# LNA.net
KiCad netlist of a schematic drawn in EAGLE
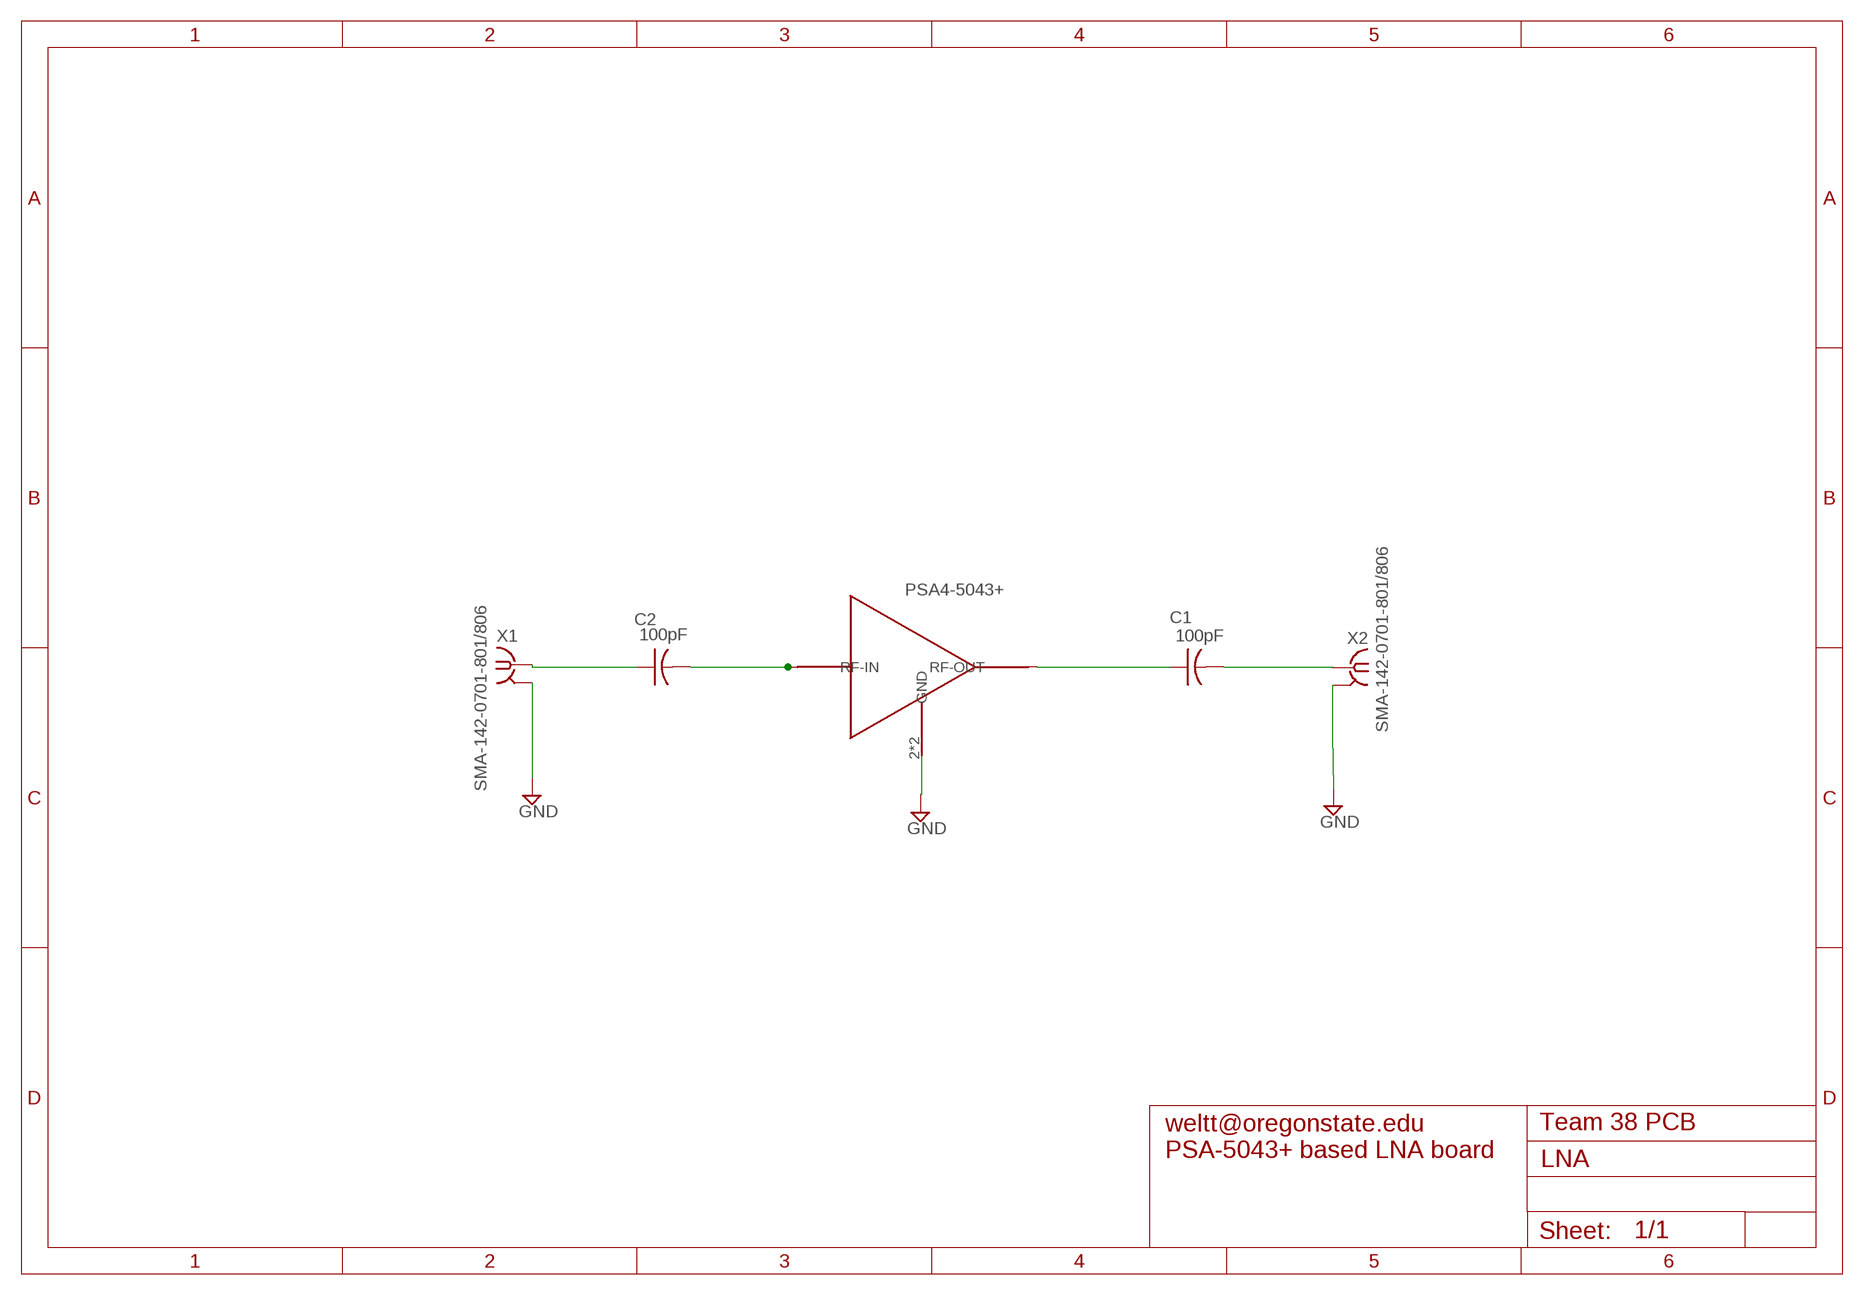
[diagram p0: schematic, sheet 1]

(export (version "E")
  (design (tool "Eeschema 10.0.6"))
  (components
    (comp (ref "C1")
      (value "100pF")
      (footprint "eagle-import:C0402K")
      (libsource (lib "eagle-import") (part "C-USC0402K"))
    )
    (comp (ref "C2")
      (value "100pF")
      (footprint "eagle-import:C0402K")
      (libsource (lib "eagle-import") (part "C-USC0402K"))
    )
    (comp (ref "MMM1362")
      (value "PSA4-5043+")
      (footprint "eagle-import:PSA4-5043+")
      (fields
        (field (name "MF") "Mini-Circuits")
        (field (name "MP") "PSA4-5043+")
        (field (name "PACKAGE") "MMM1362")
        (field (name "PRICE") "2.50")
        (field (name "SPICEPREFIX") "M")
      )
      (libsource (lib "eagle-import") (part "PSA4-5043+"))
    )
    (comp (ref "X1")
      (value "SMA-142-0701-801/806")
      (footprint "eagle-import:J502-ND-142-0701-801_806")
      (fields (field (name "MF") "JOHNSON COMPONENTS") (field (name "MPN") "142-0701-801"))
      (libsource (lib "eagle-import") (part "SMA-142-0701-801/806"))
    )
    (comp (ref "X2")
      (value "SMA-142-0701-801/806")
      (footprint "eagle-import:J502-ND-142-0701-801_806")
      (fields (field (name "MF") "JOHNSON COMPONENTS") (field (name "MPN") "142-0701-801"))
      (libsource (lib "eagle-import") (part "SMA-142-0701-801/806"))
    )
  )
  (nets
    (net (code "1") (name "GND") (class "Default")
      (node (ref "MMM1362") (pin "2") (pinfunction "GND_2") (pintype "bidirectional"))
      (node (ref "MMM1362") (pin "4") (pinfunction "GND_4") (pintype "bidirectional"))
      (node (ref "X1") (pin "G@1") (pinfunction "2_G@1") (pintype "passive"))
      (node (ref "X1") (pin "G@2") (pinfunction "2_G@2") (pintype "passive"))
      (node (ref "X1") (pin "G@3") (pinfunction "2_G@3") (pintype "passive"))
      (node (ref "X1") (pin "G@4") (pinfunction "2_G@4") (pintype "passive"))
      (node (ref "X2") (pin "G@1") (pinfunction "2_G@1") (pintype "passive"))
      (node (ref "X2") (pin "G@2") (pinfunction "2_G@2") (pintype "passive"))
      (node (ref "X2") (pin "G@3") (pinfunction "2_G@3") (pintype "passive"))
      (node (ref "X2") (pin "G@4") (pinfunction "2_G@4") (pintype "passive"))
    )
    (net (code "2") (name "Net-(C1-Pad2)") (class "Default")
      (node (ref "C1") (pin "2") (pinfunction "2_2") (pintype "passive"))
      (node (ref "X2") (pin "1") (pinfunction "1_1") (pintype "passive"))
    )
    (net (code "3") (name "Net-(C2-Pad1)") (class "Default")
      (node (ref "C2") (pin "1") (pinfunction "1_1") (pintype "passive"))
      (node (ref "X1") (pin "1") (pinfunction "1_1") (pintype "passive"))
    )
    (net (code "4") (name "Net-(MMM1362-RF-IN)") (class "Default")
      (node (ref "C2") (pin "2") (pinfunction "2_2") (pintype "passive"))
      (node (ref "MMM1362") (pin "3") (pinfunction "RF-IN_3") (pintype "bidirectional"))
    )
    (net (code "5") (name "Net-(MMM1362-RF-OUT)") (class "Default")
      (node (ref "C1") (pin "1") (pinfunction "1_1") (pintype "passive"))
      (node (ref "MMM1362") (pin "1") (pinfunction "RF-OUT_1") (pintype "bidirectional"))
    )
  )
)
